# IM920Receiver.net
KiCad netlist of a schematic drawn in EAGLE
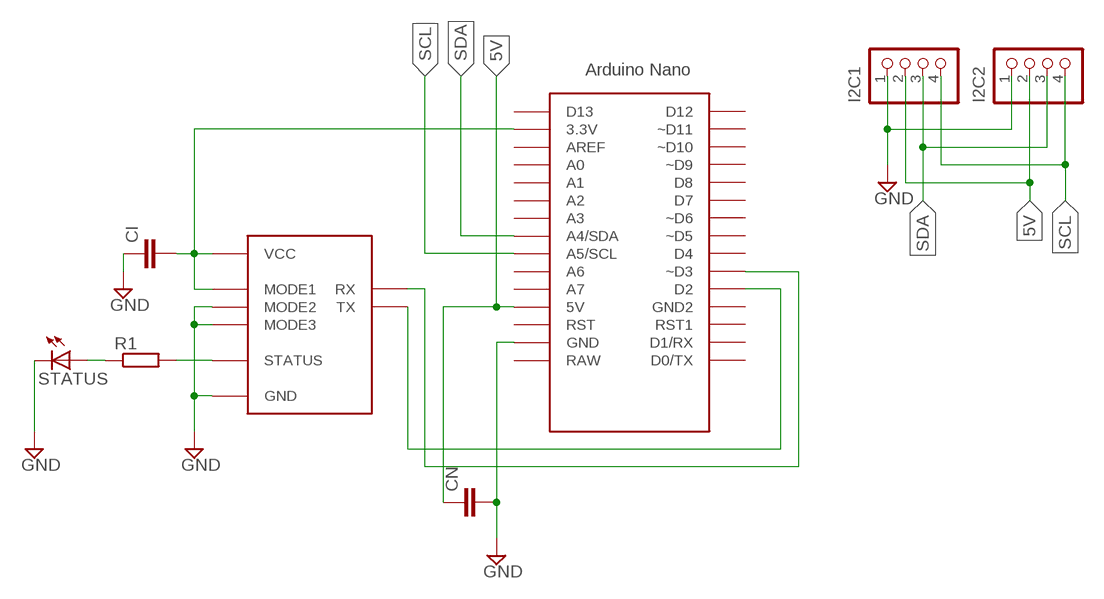
[diagram p0: schematic, sheet 1]

(export (version "E")
  (design (tool "Eeschema 10.0.6"))
  (components
    (comp (ref "CI")
      (value "C2.5/2")
      (footprint "eagle-import:C2.5-2")
      (libsource (lib "eagle-import") (part "C2.5/2"))
    )
    (comp (ref "CN")
      (value "C2.5/2")
      (footprint "eagle-import:C2.5-2")
      (libsource (lib "eagle-import") (part "C2.5/2"))
    )
    (comp (ref "I2C1")
      (value "B4B-XH-A")
      (footprint "eagle-import:B4B-XH-A")
      (libsource (lib "eagle-import") (part "B4B-XH-A"))
    )
    (comp (ref "I2C2")
      (value "B4B-XH-A")
      (footprint "eagle-import:B4B-XH-A")
      (libsource (lib "eagle-import") (part "B4B-XH-A"))
    )
    (comp (ref "R1")
      (value "R-EU_0204/7")
      (footprint "eagle-import:0204_7")
      (libsource (lib "eagle-import") (part "R-EU_0204/7"))
    )
    (comp (ref "STATUS")
      (value "LED3MM")
      (footprint "eagle-import:LED3MM")
      (libsource (lib "eagle-import") (part "LED3MM"))
    )
    (comp (ref "U$1")
      (value "IM920")
      (footprint "eagle-import:IM920")
      (libsource (lib "eagle-import") (part "IM920"))
    )
    (comp (ref "U$2")
      (value "NANO")
      (footprint "eagle-import:NANO")
      (libsource (lib "eagle-import") (part "NANO"))
    )
  )
  (nets
    (net (code "1") (name "5V") (class "Default")
      (node (ref "CN") (pin "1") (pinfunction "1_1") (pintype "passive"))
      (node (ref "I2C1") (pin "2") (pinfunction "2_2") (pintype "passive"))
      (node (ref "I2C2") (pin "2") (pinfunction "2_2") (pintype "passive"))
      (node (ref "U$2") (pin "5V") (pinfunction "5V_5V") (pintype "bidirectional"))
    )
    (net (code "2") (name "GND") (class "Default")
      (node (ref "CI") (pin "1") (pinfunction "1_1") (pintype "passive"))
      (node (ref "CN") (pin "2") (pinfunction "2_2") (pintype "passive"))
      (node (ref "I2C1") (pin "1") (pinfunction "1_1") (pintype "passive"))
      (node (ref "I2C2") (pin "1") (pinfunction "1_1") (pintype "passive"))
      (node (ref "STATUS") (pin "K") (pinfunction "C_K") (pintype "passive"))
      (node (ref "U$1") (pin "GND") (pinfunction "GND_GND") (pintype "bidirectional"))
      (node (ref "U$1") (pin "MODE2") (pinfunction "MODE2_MODE2") (pintype "bidirectional"))
      (node (ref "U$1") (pin "MODE3") (pinfunction "MODE3_MODE3") (pintype "bidirectional"))
      (node (ref "U$2") (pin "GND") (pinfunction "GND_GND") (pintype "bidirectional"))
    )
    (net (code "3") (name "Net-(CI-Pad2)") (class "Default")
      (node (ref "CI") (pin "2") (pinfunction "2_2") (pintype "passive"))
      (node (ref "U$1") (pin "MODE1") (pinfunction "MODE1_MODE1") (pintype "bidirectional"))
      (node (ref "U$1") (pin "VCC") (pinfunction "VCC_VCC") (pintype "bidirectional"))
      (node (ref "U$2") (pin "3.3V") (pinfunction "3.3V_3.3V") (pintype "bidirectional"))
    )
    (net (code "4") (name "Net-(R1-Pad1)") (class "Default")
      (node (ref "R1") (pin "1") (pinfunction "1_1") (pintype "passive"))
      (node (ref "STATUS") (pin "A") (pinfunction "A_A") (pintype "passive"))
    )
    (net (code "5") (name "Net-(R1-Pad2)") (class "Default")
      (node (ref "R1") (pin "2") (pinfunction "2_2") (pintype "passive"))
      (node (ref "U$1") (pin "STATUS") (pinfunction "STATUS_STATUS") (pintype "bidirectional"))
    )
    (net (code "6") (name "Net-(U$1-PadTX)") (class "Default")
      (node (ref "U$1") (pin "TX") (pinfunction "TX_TX") (pintype "bidirectional"))
      (node (ref "U$2") (pin "D2") (pinfunction "D2_D2") (pintype "bidirectional"))
    )
    (net (code "7") (name "Net-(U$2-~{D3})") (class "Default")
      (node (ref "U$1") (pin "RX") (pinfunction "RX_RX") (pintype "bidirectional"))
      (node (ref "U$2") (pin "D3") (pinfunction "~{D3}_D3") (pintype "bidirectional"))
    )
    (net (code "8") (name "SCL") (class "Default")
      (node (ref "I2C1") (pin "4") (pinfunction "4_4") (pintype "passive"))
      (node (ref "I2C2") (pin "4") (pinfunction "4_4") (pintype "passive"))
      (node (ref "U$2") (pin "A5") (pinfunction "A5/SCL_A5") (pintype "bidirectional"))
    )
    (net (code "9") (name "SDA") (class "Default")
      (node (ref "I2C1") (pin "3") (pinfunction "3_3") (pintype "passive"))
      (node (ref "I2C2") (pin "3") (pinfunction "3_3") (pintype "passive"))
      (node (ref "U$2") (pin "A4") (pinfunction "A4/SDA_A4") (pintype "bidirectional"))
    )
    (net (code "10") (name "unconnected-(U$2-D0{slash}TX-PadTX0)") (class "Default")
      (node (ref "U$2") (pin "TX0") (pinfunction "D0/TX_TX0") (pintype "bidirectional"))
    )
    (net (code "11") (name "unconnected-(U$2-D1{slash}RX-PadRX1)") (class "Default")
      (node (ref "U$2") (pin "RX1") (pinfunction "D1/RX_RX1") (pintype "bidirectional"))
    )
    (net (code "12") (name "unconnected-(U$2-GND2-PadGND1)") (class "Default")
      (node (ref "U$2") (pin "GND1") (pinfunction "GND2_GND1") (pintype "bidirectional"))
    )
    (net (code "13") (name "unconnected-(U$2-PadA0)") (class "Default")
      (node (ref "U$2") (pin "A0") (pinfunction "A0_A0") (pintype "bidirectional"))
    )
    (net (code "14") (name "unconnected-(U$2-PadA1)") (class "Default")
      (node (ref "U$2") (pin "A1") (pinfunction "A1_A1") (pintype "bidirectional"))
    )
    (net (code "15") (name "unconnected-(U$2-PadA2)") (class "Default")
      (node (ref "U$2") (pin "A2") (pinfunction "A2_A2") (pintype "bidirectional"))
    )
    (net (code "16") (name "unconnected-(U$2-PadA3)") (class "Default")
      (node (ref "U$2") (pin "A3") (pinfunction "A3_A3") (pintype "bidirectional"))
    )
    (net (code "17") (name "unconnected-(U$2-PadA6)") (class "Default")
      (node (ref "U$2") (pin "A6") (pinfunction "A6_A6") (pintype "bidirectional"))
    )
    (net (code "18") (name "unconnected-(U$2-PadA7)") (class "Default")
      (node (ref "U$2") (pin "A7") (pinfunction "A7_A7") (pintype "bidirectional"))
    )
    (net (code "19") (name "unconnected-(U$2-PadAREF)") (class "Default")
      (node (ref "U$2") (pin "AREF") (pinfunction "AREF_AREF") (pintype "bidirectional"))
    )
    (net (code "20") (name "unconnected-(U$2-PadD4)") (class "Default")
      (node (ref "U$2") (pin "D4") (pinfunction "D4_D4") (pintype "bidirectional"))
    )
    (net (code "21") (name "unconnected-(U$2-PadD7)") (class "Default")
      (node (ref "U$2") (pin "D7") (pinfunction "D7_D7") (pintype "bidirectional"))
    )
    (net (code "22") (name "unconnected-(U$2-PadD8)") (class "Default")
      (node (ref "U$2") (pin "D8") (pinfunction "D8_D8") (pintype "bidirectional"))
    )
    (net (code "23") (name "unconnected-(U$2-PadD12)") (class "Default")
      (node (ref "U$2") (pin "D12") (pinfunction "D12_D12") (pintype "bidirectional"))
    )
    (net (code "24") (name "unconnected-(U$2-PadD13)") (class "Default")
      (node (ref "U$2") (pin "D13") (pinfunction "D13_D13") (pintype "bidirectional"))
    )
    (net (code "25") (name "unconnected-(U$2-PadRAW)") (class "Default")
      (node (ref "U$2") (pin "RAW") (pinfunction "RAW_RAW") (pintype "bidirectional"))
    )
    (net (code "26") (name "unconnected-(U$2-PadRST)") (class "Default")
      (node (ref "U$2") (pin "RST") (pinfunction "RST_RST") (pintype "bidirectional"))
    )
    (net (code "27") (name "unconnected-(U$2-PadRST1)") (class "Default")
      (node (ref "U$2") (pin "RST1") (pinfunction "RST1_RST1") (pintype "bidirectional"))
    )
    (net (code "28") (name "unconnected-(U$2-~{D5}-PadD5)") (class "Default")
      (node (ref "U$2") (pin "D5") (pinfunction "~{D5}_D5") (pintype "bidirectional"))
    )
    (net (code "29") (name "unconnected-(U$2-~{D6}-PadD6)") (class "Default")
      (node (ref "U$2") (pin "D6") (pinfunction "~{D6}_D6") (pintype "bidirectional"))
    )
    (net (code "30") (name "unconnected-(U$2-~{D9}-PadD9)") (class "Default")
      (node (ref "U$2") (pin "D9") (pinfunction "~{D9}_D9") (pintype "bidirectional"))
    )
    (net (code "31") (name "unconnected-(U$2-~{D10}-PadD10)") (class "Default")
      (node (ref "U$2") (pin "D10") (pinfunction "~{D10}_D10") (pintype "bidirectional"))
    )
    (net (code "32") (name "unconnected-(U$2-~{D11}-PadD11)") (class "Default")
      (node (ref "U$2") (pin "D11") (pinfunction "~{D11}_D11") (pintype "bidirectional"))
    )
  )
)
